# Versorgungsspannung.net
KiCad netlist of a schematic drawn in Altium Designer
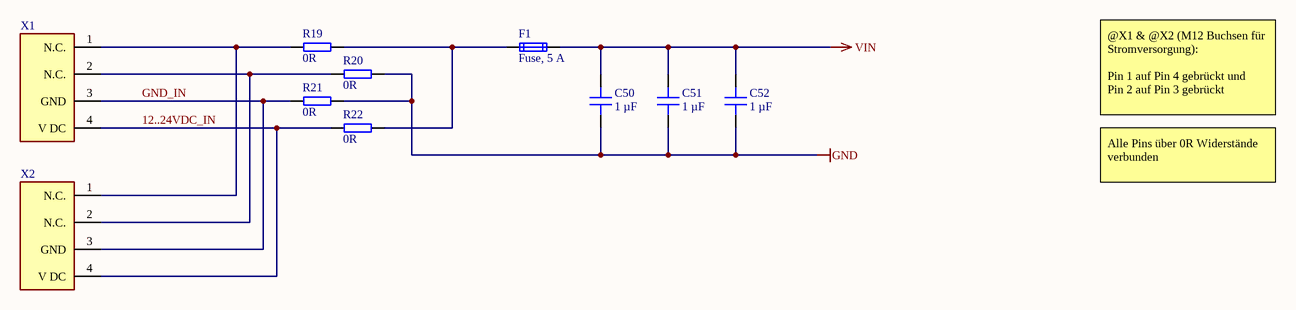
[diagram p0: Versorgungsspannung.SchDoc]

(export (version "E")
  (design (tool "Eeschema 10.0.6"))
  (components
    (comp (ref "C50")
      (value "1 µF")
      (footprint "C_0603")
      (description "50V 1uF X5R ±10% 0603  Multilayer Ceramic Capacitors MLCC - SMD/SMT ROHS")
      (fields
        (field (name "MANUFACTURER") "Samsung Electro-Mechanics")
        (field (name "MANUFACTURER PART NUMBER") "CL10A105KB8NNNC")
        (field (name "CREATED FROM") "MGremer")
      )
      (libsource (lib "user") (part "Capacitor"))
    )
    (comp (ref "C51")
      (value "1 µF")
      (footprint "C_0603")
      (description "50V 1uF X5R ±10% 0603  Multilayer Ceramic Capacitors MLCC - SMD/SMT ROHS")
      (fields
        (field (name "MANUFACTURER") "Samsung Electro-Mechanics")
        (field (name "MANUFACTURER PART NUMBER") "CL10A105KB8NNNC")
        (field (name "CREATED FROM") "MGremer")
      )
      (libsource (lib "user") (part "Capacitor"))
    )
    (comp (ref "C52")
      (value "1 µF")
      (footprint "C_0603")
      (description "50V 1uF X5R ±10% 0603  Multilayer Ceramic Capacitors MLCC - SMD/SMT ROHS")
      (fields
        (field (name "MANUFACTURER") "Samsung Electro-Mechanics")
        (field (name "MANUFACTURER PART NUMBER") "CL10A105KB8NNNC")
        (field (name "CREATED FROM") "MGremer")
      )
      (libsource (lib "user") (part "Capacitor"))
    )
    (comp (ref "F1")
      (value "Fuse, 5 A")
      (footprint "0154xxx")
      (description "Fuse OMNI BLOK 154")
      (fields
        (field (name "MANUFACTURER PART NUMBER") "0154005.DR")
        (field (name "MANUFACTURER") "Littlefuse")
        (field (name "CREATED FROM") "MGremer")
      )
      (libsource (lib "user") (part "Polyswitch"))
    )
    (comp (ref "R19")
      (value "0R")
      (footprint "RES 1206_3216")
      (description "250mW Thick Film Resistors ±800ppm/℃ ±1% 0Ω 1206 Chip Resistor - Surface Mount ROHS")
      (fields
        (field (name "MANUFACTURER PART NUMBER") "1206W4F0000T5E")
        (field (name "MANUFACTURER") "UNI-ROYAL")
        (field (name "CREATED FROM") "AGeiger")
      )
      (libsource (lib "user") (part "Resistor"))
    )
    (comp (ref "R20")
      (value "0R")
      (footprint "RES 1206_3216")
      (description "250mW Thick Film Resistors ±800ppm/℃ ±1% 0Ω 1206 Chip Resistor - Surface Mount ROHS")
      (fields
        (field (name "MANUFACTURER PART NUMBER") "1206W4F0000T5E")
        (field (name "MANUFACTURER") "UNI-ROYAL")
        (field (name "CREATED FROM") "AGeiger")
      )
      (libsource (lib "user") (part "Resistor"))
    )
    (comp (ref "R21")
      (value "0R")
      (footprint "RES 1206_3216")
      (description "250mW Thick Film Resistors ±800ppm/℃ ±1% 0Ω 1206 Chip Resistor - Surface Mount ROHS")
      (fields
        (field (name "MANUFACTURER PART NUMBER") "1206W4F0000T5E")
        (field (name "MANUFACTURER") "UNI-ROYAL")
        (field (name "CREATED FROM") "AGeiger")
      )
      (libsource (lib "user") (part "Resistor"))
    )
    (comp (ref "R22")
      (value "0R")
      (footprint "RES 1206_3216")
      (description "250mW Thick Film Resistors ±800ppm/℃ ±1% 0Ω 1206 Chip Resistor - Surface Mount ROHS")
      (fields
        (field (name "MANUFACTURER PART NUMBER") "1206W4F0000T5E")
        (field (name "MANUFACTURER") "UNI-ROYAL")
        (field (name "CREATED FROM") "AGeiger")
      )
      (libsource (lib "user") (part "Resistor"))
    )
    (comp (ref "X1")
      (value "CAZN_M12-P4A-GPL_M12")
      (footprint "CAZN_M12-P4A-GPL_M12")
      (fields
        (field (name "MANUFACTURER") "CAZN")
        (field (name "LCSC PART NUMBER") "C19108992")
        (field (name "CREATED FROM") "TGaupp")
      )
      (libsource (lib "user") (part "CAZN_M12-P4A-GPL_M12"))
    )
    (comp (ref "X2")
      (value "CAZN_M12-P4A-GPL_M12")
      (footprint "CAZN_M12-P4A-GPL_M12")
      (fields
        (field (name "MANUFACTURER") "CAZN")
        (field (name "LCSC PART NUMBER") "C19108992")
        (field (name "CREATED FROM") "TGaupp")
      )
      (libsource (lib "user") (part "CAZN_M12-P4A-GPL_M12"))
    )
  )
  (nets
    (net (code "1") (name "/12..24VDC_IN") (class "Default")
      (node (ref "R22") (pin "1") (pinfunction "1_1") (pintype "passive"))
      (node (ref "X1") (pin "4") (pinfunction "V_DC_4") (pintype "power_in"))
      (node (ref "X2") (pin "4") (pinfunction "V_DC_4") (pintype "power_in"))
    )
    (net (code "2") (name "/GND_IN") (class "Default")
      (node (ref "R21") (pin "1") (pinfunction "1_1") (pintype "passive"))
      (node (ref "X1") (pin "3") (pinfunction "GND_3") (pintype "power_in"))
      (node (ref "X2") (pin "3") (pinfunction "GND_3") (pintype "power_in"))
    )
    (net (code "3") (name "GND") (class "Default")
      (node (ref "C50") (pin "2") (pinfunction "2_2") (pintype "passive"))
      (node (ref "C51") (pin "2") (pinfunction "2_2") (pintype "passive"))
      (node (ref "C52") (pin "2") (pinfunction "2_2") (pintype "passive"))
      (node (ref "R20") (pin "2") (pinfunction "2_2") (pintype "passive"))
      (node (ref "R21") (pin "2") (pinfunction "2_2") (pintype "passive"))
    )
    (net (code "4") (name "Net-(F1-Pad1)") (class "Default")
      (node (ref "F1") (pin "1") (pinfunction "1_1") (pintype "passive"))
      (node (ref "R19") (pin "2") (pinfunction "2_2") (pintype "passive"))
      (node (ref "R22") (pin "2") (pinfunction "2_2") (pintype "passive"))
    )
    (net (code "5") (name "Net-(R19-Pad1)") (class "Default")
      (node (ref "R19") (pin "1") (pinfunction "1_1") (pintype "passive"))
      (node (ref "X1") (pin "1") (pinfunction "N.C._1") (pintype "passive"))
      (node (ref "X2") (pin "1") (pinfunction "N.C._1") (pintype "passive"))
    )
    (net (code "6") (name "Net-(R20-Pad1)") (class "Default")
      (node (ref "R20") (pin "1") (pinfunction "1_1") (pintype "passive"))
      (node (ref "X1") (pin "2") (pinfunction "N.C._2") (pintype "passive"))
      (node (ref "X2") (pin "2") (pinfunction "N.C._2") (pintype "passive"))
    )
    (net (code "7") (name "VIN") (class "Default")
      (node (ref "C50") (pin "1") (pinfunction "1_1") (pintype "passive"))
      (node (ref "C51") (pin "1") (pinfunction "1_1") (pintype "passive"))
      (node (ref "C52") (pin "1") (pinfunction "1_1") (pintype "passive"))
      (node (ref "F1") (pin "2") (pinfunction "2_2") (pintype "passive"))
    )
  )
)
